# 2KbeaconDetectorV1_1.net
KiCad netlist of a schematic drawn in EAGLE
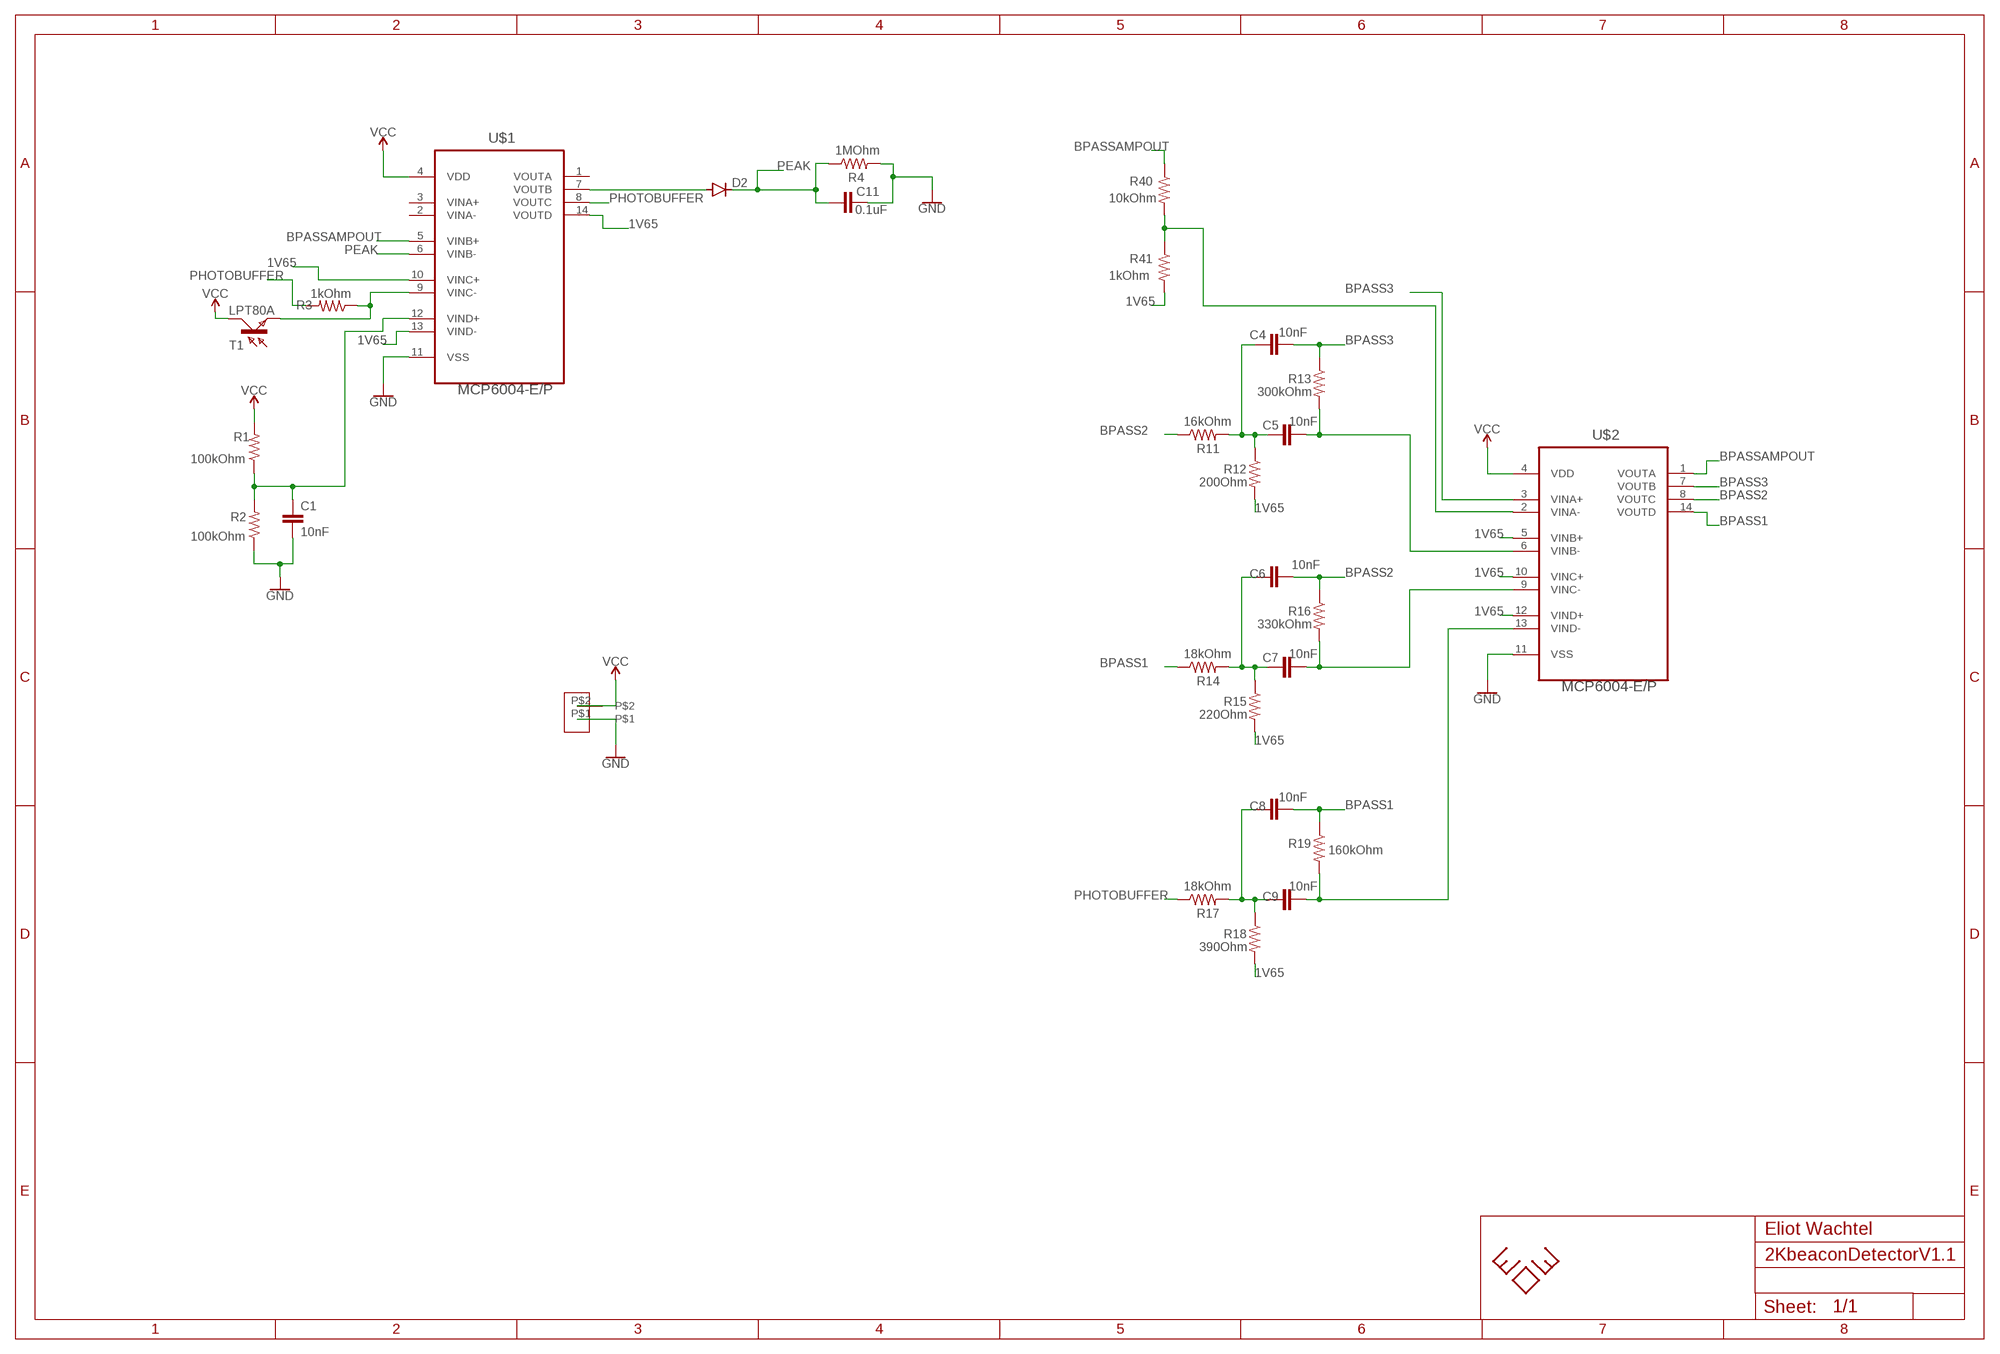
[diagram p0: schematic, sheet 1]

(export (version "E")
  (design (tool "Eeschema 10.0.6"))
  (components
    (comp (ref "C1")
      (value "10nF")
      (footprint "eagle-import:C5B2.5")
      (libsource (lib "eagle-import") (part "C5/2.5"))
    )
    (comp (ref "C4")
      (value "10nF")
      (footprint "eagle-import:C5B2.5")
      (libsource (lib "eagle-import") (part "C5/2.5"))
    )
    (comp (ref "C5")
      (value "10nF")
      (footprint "eagle-import:C5B2.5")
      (libsource (lib "eagle-import") (part "C5/2.5"))
    )
    (comp (ref "C6")
      (value "10nF")
      (footprint "eagle-import:C5B2.5")
      (libsource (lib "eagle-import") (part "C5/2.5"))
    )
    (comp (ref "C7")
      (value "10nF")
      (footprint "eagle-import:C5B2.5")
      (libsource (lib "eagle-import") (part "C5/2.5"))
    )
    (comp (ref "C8")
      (value "10nF")
      (footprint "eagle-import:C5B2.5")
      (libsource (lib "eagle-import") (part "C5/2.5"))
    )
    (comp (ref "C9")
      (value "10nF")
      (footprint "eagle-import:C5B2.5")
      (libsource (lib "eagle-import") (part "C5/2.5"))
    )
    (comp (ref "C11")
      (value "0.1uF")
      (footprint "eagle-import:C5B2.5")
      (libsource (lib "eagle-import") (part "C5/2.5"))
    )
    (comp (ref "D2")
      (value "DIODE-D-7.5")
      (footprint "eagle-import:D-7.5")
      (libsource (lib "eagle-import") (part "DIODE-D-7.5"))
    )
    (comp (ref "R1")
      (value "100kOhm")
      (footprint "eagle-import:0204_5")
      (libsource (lib "eagle-import") (part "R-US_0204/5"))
    )
    (comp (ref "R2")
      (value "100kOhm")
      (footprint "eagle-import:0204V")
      (libsource (lib "eagle-import") (part "R-US_0204/2V"))
    )
    (comp (ref "R3")
      (value "1kOhm")
      (footprint "eagle-import:0204V")
      (libsource (lib "eagle-import") (part "R-US_0204/2V"))
    )
    (comp (ref "R4")
      (value "1MOhm")
      (footprint "eagle-import:0204_5")
      (libsource (lib "eagle-import") (part "R-US_0204/5"))
    )
    (comp (ref "R11")
      (value "16kOhm")
      (footprint "eagle-import:0204_5")
      (libsource (lib "eagle-import") (part "R-US_0204/5"))
    )
    (comp (ref "R12")
      (value "200Ohm")
      (footprint "eagle-import:0204_7")
      (libsource (lib "eagle-import") (part "R-US_0204/7"))
    )
    (comp (ref "R13")
      (value "300kOhm")
      (footprint "eagle-import:0204V")
      (libsource (lib "eagle-import") (part "R-US_0204/2V"))
    )
    (comp (ref "R14")
      (value "18kOhm")
      (footprint "eagle-import:0204_5")
      (libsource (lib "eagle-import") (part "R-US_0204/5"))
    )
    (comp (ref "R15")
      (value "220Ohm")
      (footprint "eagle-import:0204_7")
      (libsource (lib "eagle-import") (part "R-US_0204/7"))
    )
    (comp (ref "R16")
      (value "330kOhm")
      (footprint "eagle-import:0204V")
      (libsource (lib "eagle-import") (part "R-US_0204/2V"))
    )
    (comp (ref "R17")
      (value "18kOhm")
      (footprint "eagle-import:0204_5")
      (libsource (lib "eagle-import") (part "R-US_0204/5"))
    )
    (comp (ref "R18")
      (value "390Ohm")
      (footprint "eagle-import:0204_5")
      (libsource (lib "eagle-import") (part "R-US_0204/5"))
    )
    (comp (ref "R19")
      (value "160kOhm")
      (footprint "eagle-import:0204V")
      (libsource (lib "eagle-import") (part "R-US_0204/2V"))
    )
    (comp (ref "R40")
      (value "10kOhm")
      (footprint "eagle-import:0204_7")
      (libsource (lib "eagle-import") (part "R-US_0204/7"))
    )
    (comp (ref "R41")
      (value "1kOhm")
      (footprint "eagle-import:0204_7")
      (libsource (lib "eagle-import") (part "R-US_0204/7"))
    )
    (comp (ref "T1")
      (value "LPT80A")
      (footprint "eagle-import:LPT80A")
      (libsource (lib "eagle-import") (part "LPT80A"))
    )
    (comp (ref "U$1")
      (value "MCP6004-E/P")
      (footprint "eagle-import:DIP254P762X533-14")
      (fields
        (field (name "DIGI-KEY_PART_NUMBER") "MCP6004-E/P-ND")
        (field (name "MF") "Microchip Technology")
      )
      (libsource (lib "eagle-import") (part "MCP6004-E/P"))
    )
    (comp (ref "U$2")
      (value "MCP6004-E/P")
      (footprint "eagle-import:DIP254P762X533-14")
      (fields
        (field (name "DIGI-KEY_PART_NUMBER") "MCP6004-E/P-ND")
        (field (name "MF") "Microchip Technology")
      )
      (libsource (lib "eagle-import") (part "MCP6004-E/P"))
    )
    (comp (ref "U$4")
      (value "WIRECONNECT2PIN")
      (footprint "eagle-import:WIRECONNECT2PIN")
      (libsource (lib "eagle-import") (part "WIRECONNECT2PIN"))
    )
  )
  (nets
    (net (code "1") (name "/1V65") (class "Default")
      (node (ref "R12") (pin "2") (pinfunction "2_2") (pintype "passive"))
      (node (ref "R15") (pin "2") (pinfunction "2_2") (pintype "passive"))
      (node (ref "R18") (pin "2") (pinfunction "2_2") (pintype "passive"))
      (node (ref "R41") (pin "2") (pinfunction "2_2") (pintype "passive"))
      (node (ref "U$1") (pin "10") (pinfunction "VINC+_10") (pintype "input"))
      (node (ref "U$1") (pin "13") (pinfunction "VIND-_13") (pintype "input"))
      (node (ref "U$1") (pin "14") (pinfunction "VOUTD_14") (pintype "output"))
      (node (ref "U$2") (pin "10") (pinfunction "VINC+_10") (pintype "input"))
      (node (ref "U$2") (pin "12") (pinfunction "VIND+_12") (pintype "input"))
      (node (ref "U$2") (pin "5") (pinfunction "VINB+_5") (pintype "input"))
    )
    (net (code "2") (name "/BPASS1") (class "Default")
      (node (ref "C8") (pin "2") (pinfunction "2_2") (pintype "passive"))
      (node (ref "R14") (pin "1") (pinfunction "1_1") (pintype "passive"))
      (node (ref "R19") (pin "1") (pinfunction "1_1") (pintype "passive"))
      (node (ref "U$2") (pin "14") (pinfunction "VOUTD_14") (pintype "output"))
    )
    (net (code "3") (name "/BPASS2") (class "Default")
      (node (ref "C6") (pin "2") (pinfunction "2_2") (pintype "passive"))
      (node (ref "R11") (pin "1") (pinfunction "1_1") (pintype "passive"))
      (node (ref "R16") (pin "1") (pinfunction "1_1") (pintype "passive"))
      (node (ref "U$2") (pin "8") (pinfunction "VOUTC_8") (pintype "output"))
    )
    (net (code "4") (name "/BPASS3") (class "Default")
      (node (ref "C4") (pin "2") (pinfunction "2_2") (pintype "passive"))
      (node (ref "R13") (pin "1") (pinfunction "1_1") (pintype "passive"))
      (node (ref "U$2") (pin "3") (pinfunction "VINA+_3") (pintype "input"))
      (node (ref "U$2") (pin "7") (pinfunction "VOUTB_7") (pintype "output"))
    )
    (net (code "5") (name "/BPASSAMPOUT") (class "Default")
      (node (ref "R40") (pin "1") (pinfunction "1_1") (pintype "passive"))
      (node (ref "U$1") (pin "5") (pinfunction "VINB+_5") (pintype "input"))
      (node (ref "U$2") (pin "1") (pinfunction "VOUTA_1") (pintype "output"))
    )
    (net (code "6") (name "/PEAK") (class "Default")
      (node (ref "C11") (pin "1") (pinfunction "1_1") (pintype "passive"))
      (node (ref "D2") (pin "C") (pinfunction "C_C") (pintype "passive"))
      (node (ref "R4") (pin "1") (pinfunction "1_1") (pintype "passive"))
      (node (ref "U$1") (pin "6") (pinfunction "VINB-_6") (pintype "input"))
    )
    (net (code "7") (name "/PHOTOBUFFER") (class "Default")
      (node (ref "R17") (pin "1") (pinfunction "1_1") (pintype "passive"))
      (node (ref "R3") (pin "2") (pinfunction "2_2") (pintype "passive"))
      (node (ref "U$1") (pin "8") (pinfunction "VOUTC_8") (pintype "output"))
    )
    (net (code "8") (name "GND") (class "Default")
      (node (ref "C1") (pin "2") (pinfunction "2_2") (pintype "passive"))
      (node (ref "C11") (pin "2") (pinfunction "2_2") (pintype "passive"))
      (node (ref "R2") (pin "1") (pinfunction "1_1") (pintype "passive"))
      (node (ref "R4") (pin "2") (pinfunction "2_2") (pintype "passive"))
      (node (ref "U$1") (pin "11") (pinfunction "VSS_11") (pintype "power_in"))
      (node (ref "U$2") (pin "11") (pinfunction "VSS_11") (pintype "power_in"))
      (node (ref "U$4") (pin "P$1") (pinfunction "P$1_P$1") (pintype "bidirectional"))
    )
    (net (code "9") (name "Net-(C4-Pad1)") (class "Default")
      (node (ref "C4") (pin "1") (pinfunction "1_1") (pintype "passive"))
      (node (ref "C5") (pin "1") (pinfunction "1_1") (pintype "passive"))
      (node (ref "R11") (pin "2") (pinfunction "2_2") (pintype "passive"))
      (node (ref "R12") (pin "1") (pinfunction "1_1") (pintype "passive"))
    )
    (net (code "10") (name "Net-(C6-Pad1)") (class "Default")
      (node (ref "C6") (pin "1") (pinfunction "1_1") (pintype "passive"))
      (node (ref "C7") (pin "1") (pinfunction "1_1") (pintype "passive"))
      (node (ref "R14") (pin "2") (pinfunction "2_2") (pintype "passive"))
      (node (ref "R15") (pin "1") (pinfunction "1_1") (pintype "passive"))
    )
    (net (code "11") (name "Net-(C8-Pad1)") (class "Default")
      (node (ref "C8") (pin "1") (pinfunction "1_1") (pintype "passive"))
      (node (ref "C9") (pin "1") (pinfunction "1_1") (pintype "passive"))
      (node (ref "R17") (pin "2") (pinfunction "2_2") (pintype "passive"))
      (node (ref "R18") (pin "1") (pinfunction "1_1") (pintype "passive"))
    )
    (net (code "12") (name "Net-(U$1-VINC-)") (class "Default")
      (node (ref "R3") (pin "1") (pinfunction "1_1") (pintype "passive"))
      (node (ref "T1") (pin "E") (pinfunction "E_E") (pintype "passive"))
      (node (ref "U$1") (pin "9") (pinfunction "VINC-_9") (pintype "input"))
    )
    (net (code "13") (name "Net-(U$1-VIND+)") (class "Default")
      (node (ref "C1") (pin "1") (pinfunction "1_1") (pintype "passive"))
      (node (ref "R1") (pin "1") (pinfunction "1_1") (pintype "passive"))
      (node (ref "R2") (pin "2") (pinfunction "2_2") (pintype "passive"))
      (node (ref "U$1") (pin "12") (pinfunction "VIND+_12") (pintype "input"))
    )
    (net (code "14") (name "Net-(U$1-VOUTB)") (class "Default")
      (node (ref "D2") (pin "A") (pinfunction "A_A") (pintype "passive"))
      (node (ref "U$1") (pin "7") (pinfunction "VOUTB_7") (pintype "output"))
    )
    (net (code "15") (name "Net-(U$2-VINA-)") (class "Default")
      (node (ref "R40") (pin "2") (pinfunction "2_2") (pintype "passive"))
      (node (ref "R41") (pin "1") (pinfunction "1_1") (pintype "passive"))
      (node (ref "U$2") (pin "2") (pinfunction "VINA-_2") (pintype "input"))
    )
    (net (code "16") (name "Net-(U$2-VINB-)") (class "Default")
      (node (ref "C5") (pin "2") (pinfunction "2_2") (pintype "passive"))
      (node (ref "R13") (pin "2") (pinfunction "2_2") (pintype "passive"))
      (node (ref "U$2") (pin "6") (pinfunction "VINB-_6") (pintype "input"))
    )
    (net (code "17") (name "Net-(U$2-VINC-)") (class "Default")
      (node (ref "C7") (pin "2") (pinfunction "2_2") (pintype "passive"))
      (node (ref "R16") (pin "2") (pinfunction "2_2") (pintype "passive"))
      (node (ref "U$2") (pin "9") (pinfunction "VINC-_9") (pintype "input"))
    )
    (net (code "18") (name "Net-(U$2-VIND-)") (class "Default")
      (node (ref "C9") (pin "2") (pinfunction "2_2") (pintype "passive"))
      (node (ref "R19") (pin "2") (pinfunction "2_2") (pintype "passive"))
      (node (ref "U$2") (pin "13") (pinfunction "VIND-_13") (pintype "input"))
    )
    (net (code "19") (name "VCC") (class "Default")
      (node (ref "R1") (pin "2") (pinfunction "2_2") (pintype "passive"))
      (node (ref "T1") (pin "C") (pinfunction "C_C") (pintype "passive"))
      (node (ref "U$1") (pin "4") (pinfunction "VDD_4") (pintype "power_in"))
      (node (ref "U$2") (pin "4") (pinfunction "VDD_4") (pintype "power_in"))
      (node (ref "U$4") (pin "P$2") (pinfunction "P$2_P$2") (pintype "bidirectional"))
    )
    (net (code "20") (name "unconnected-(U$1-VINA+-Pad3)") (class "Default")
      (node (ref "U$1") (pin "3") (pinfunction "VINA+_3") (pintype "input"))
    )
    (net (code "21") (name "unconnected-(U$1-VINA--Pad2)") (class "Default")
      (node (ref "U$1") (pin "2") (pinfunction "VINA-_2") (pintype "input"))
    )
    (net (code "22") (name "unconnected-(U$1-VOUTA-Pad1)") (class "Default")
      (node (ref "U$1") (pin "1") (pinfunction "VOUTA_1") (pintype "output"))
    )
  )
)
